# power-distribution.net
KiCad netlist of a schematic drawn in EAGLE
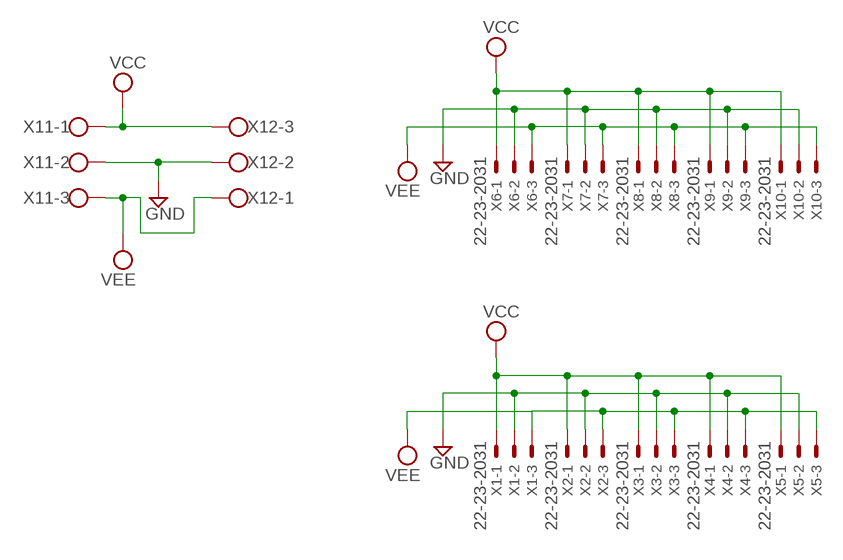
[diagram p0: schematic, sheet 1]

(export (version "E")
  (design (tool "Eeschema 10.0.6"))
  (components
    (comp (ref "X1")
      (value "22-23-2031")
      (footprint "eagle-import:22-23-2031")
      (fields (field (name "MF") "MOLEX"))
      (libsource (lib "eagle-import") (part "22-23-2031"))
    )
    (comp (ref "X2")
      (value "22-23-2031")
      (footprint "eagle-import:22-23-2031")
      (fields (field (name "MF") "MOLEX"))
      (libsource (lib "eagle-import") (part "22-23-2031"))
    )
    (comp (ref "X3")
      (value "22-23-2031")
      (footprint "eagle-import:22-23-2031")
      (fields (field (name "MF") "MOLEX"))
      (libsource (lib "eagle-import") (part "22-23-2031"))
    )
    (comp (ref "X4")
      (value "22-23-2031")
      (footprint "eagle-import:22-23-2031")
      (fields (field (name "MF") "MOLEX"))
      (libsource (lib "eagle-import") (part "22-23-2031"))
    )
    (comp (ref "X5")
      (value "22-23-2031")
      (footprint "eagle-import:22-23-2031")
      (fields (field (name "MF") "MOLEX"))
      (libsource (lib "eagle-import") (part "22-23-2031"))
    )
    (comp (ref "X6")
      (value "22-23-2031")
      (footprint "eagle-import:22-23-2031")
      (fields (field (name "MF") "MOLEX"))
      (libsource (lib "eagle-import") (part "22-23-2031"))
    )
    (comp (ref "X7")
      (value "22-23-2031")
      (footprint "eagle-import:22-23-2031")
      (fields (field (name "MF") "MOLEX"))
      (libsource (lib "eagle-import") (part "22-23-2031"))
    )
    (comp (ref "X8")
      (value "22-23-2031")
      (footprint "eagle-import:22-23-2031")
      (fields (field (name "MF") "MOLEX"))
      (libsource (lib "eagle-import") (part "22-23-2031"))
    )
    (comp (ref "X9")
      (value "22-23-2031")
      (footprint "eagle-import:22-23-2031")
      (fields (field (name "MF") "MOLEX"))
      (libsource (lib "eagle-import") (part "22-23-2031"))
    )
    (comp (ref "X10")
      (value "22-23-2031")
      (footprint "eagle-import:22-23-2031")
      (fields (field (name "MF") "MOLEX"))
      (libsource (lib "eagle-import") (part "22-23-2031"))
    )
    (comp (ref "X11")
      (value "W237-103")
      (footprint "eagle-import:W237-103")
      (fields (field (name "MPN") "237-103"))
      (libsource (lib "eagle-import") (part "W237-103"))
    )
    (comp (ref "X12")
      (value "W237-103")
      (footprint "eagle-import:W237-103")
      (fields (field (name "MPN") "237-103"))
      (libsource (lib "eagle-import") (part "W237-103"))
    )
  )
  (nets
    (net (code "1") (name "GND") (class "Default")
      (node (ref "X1") (pin "2") (pinfunction "S_2") (pintype "passive"))
      (node (ref "X10") (pin "2") (pinfunction "S_2") (pintype "passive"))
      (node (ref "X11") (pin "2") (pinfunction "KL_2") (pintype "passive"))
      (node (ref "X12") (pin "2") (pinfunction "KL_2") (pintype "passive"))
      (node (ref "X2") (pin "2") (pinfunction "S_2") (pintype "passive"))
      (node (ref "X3") (pin "2") (pinfunction "S_2") (pintype "passive"))
      (node (ref "X4") (pin "2") (pinfunction "S_2") (pintype "passive"))
      (node (ref "X5") (pin "2") (pinfunction "S_2") (pintype "passive"))
      (node (ref "X6") (pin "2") (pinfunction "S_2") (pintype "passive"))
      (node (ref "X7") (pin "2") (pinfunction "S_2") (pintype "passive"))
      (node (ref "X8") (pin "2") (pinfunction "S_2") (pintype "passive"))
      (node (ref "X9") (pin "2") (pinfunction "S_2") (pintype "passive"))
    )
    (net (code "2") (name "VCC") (class "Default")
      (node (ref "X1") (pin "1") (pinfunction "S_1") (pintype "passive"))
      (node (ref "X10") (pin "1") (pinfunction "S_1") (pintype "passive"))
      (node (ref "X11") (pin "1") (pinfunction "KL_1") (pintype "passive"))
      (node (ref "X12") (pin "3") (pinfunction "KL_3") (pintype "passive"))
      (node (ref "X2") (pin "1") (pinfunction "S_1") (pintype "passive"))
      (node (ref "X3") (pin "1") (pinfunction "S_1") (pintype "passive"))
      (node (ref "X4") (pin "1") (pinfunction "S_1") (pintype "passive"))
      (node (ref "X5") (pin "1") (pinfunction "S_1") (pintype "passive"))
      (node (ref "X6") (pin "1") (pinfunction "S_1") (pintype "passive"))
      (node (ref "X7") (pin "1") (pinfunction "S_1") (pintype "passive"))
      (node (ref "X8") (pin "1") (pinfunction "S_1") (pintype "passive"))
      (node (ref "X9") (pin "1") (pinfunction "S_1") (pintype "passive"))
    )
    (net (code "3") (name "VEE") (class "Default")
      (node (ref "X1") (pin "3") (pinfunction "S_3") (pintype "passive"))
      (node (ref "X10") (pin "3") (pinfunction "S_3") (pintype "passive"))
      (node (ref "X11") (pin "3") (pinfunction "KL_3") (pintype "passive"))
      (node (ref "X12") (pin "1") (pinfunction "KL_1") (pintype "passive"))
      (node (ref "X2") (pin "3") (pinfunction "S_3") (pintype "passive"))
      (node (ref "X3") (pin "3") (pinfunction "S_3") (pintype "passive"))
      (node (ref "X4") (pin "3") (pinfunction "S_3") (pintype "passive"))
      (node (ref "X5") (pin "3") (pinfunction "S_3") (pintype "passive"))
      (node (ref "X6") (pin "3") (pinfunction "S_3") (pintype "passive"))
      (node (ref "X7") (pin "3") (pinfunction "S_3") (pintype "passive"))
      (node (ref "X8") (pin "3") (pinfunction "S_3") (pintype "passive"))
      (node (ref "X9") (pin "3") (pinfunction "S_3") (pintype "passive"))
    )
  )
)
